# mother_card_cs_524pm.net
KiCad netlist of a schematic drawn in EAGLE
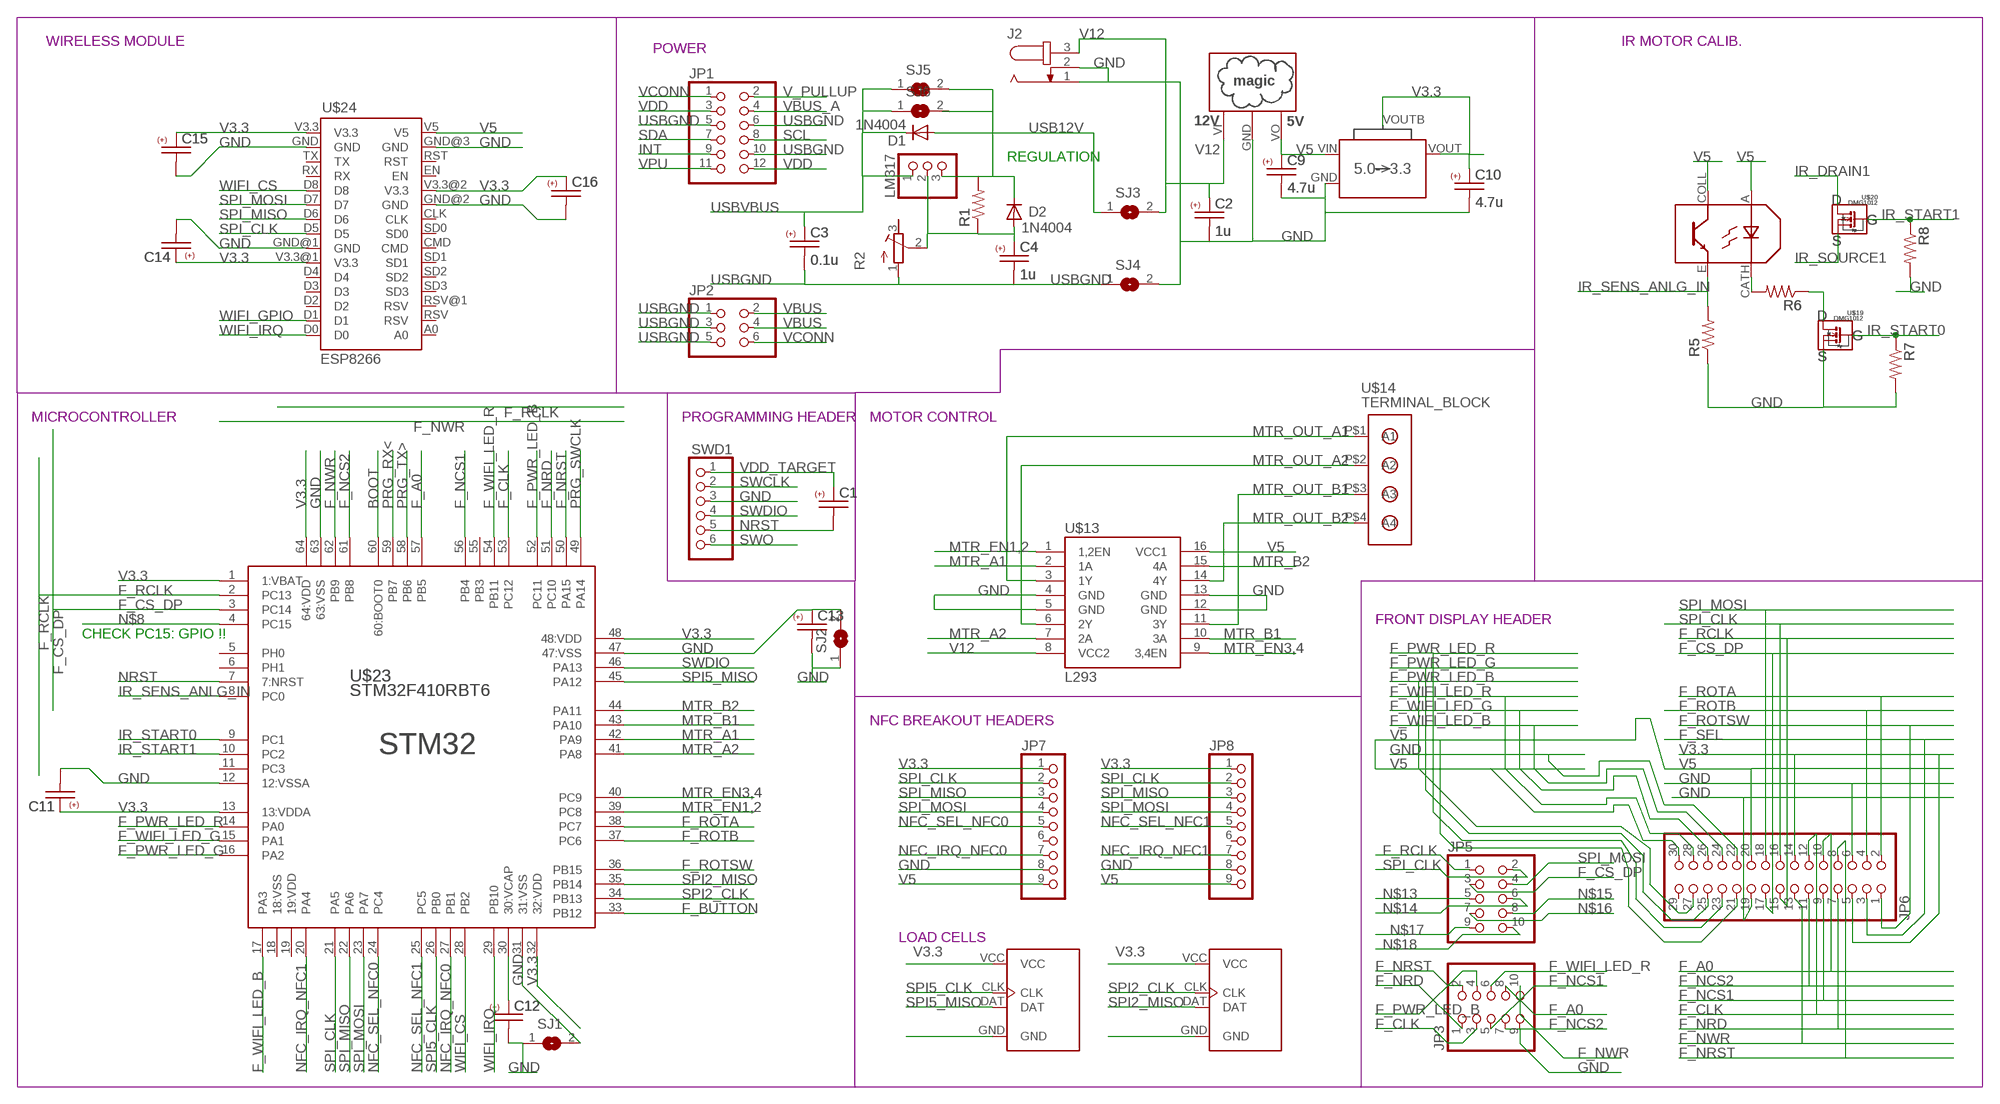
[diagram p0: schematic, sheet 1]

(export (version "E")
  (design (tool "Eeschema 10.0.6"))
  (components
    (comp (ref "C1")
      (value "C-USC0805")
      (footprint "eagle-import:C0805")
      (libsource (lib "eagle-import") (part "C-USC0805"))
    )
    (comp (ref "C2")
      (value "1u")
      (footprint "eagle-import:C0805")
      (libsource (lib "eagle-import") (part "C-USC0805"))
    )
    (comp (ref "C3")
      (value "0.1u")
      (footprint "eagle-import:C0805")
      (libsource (lib "eagle-import") (part "C-USC0805"))
    )
    (comp (ref "C4")
      (value "1u")
      (footprint "eagle-import:C0805")
      (libsource (lib "eagle-import") (part "C-USC0805"))
    )
    (comp (ref "C9")
      (value "4.7u")
      (footprint "eagle-import:C0805")
      (libsource (lib "eagle-import") (part "C-USC0805"))
    )
    (comp (ref "C10")
      (value "4.7u")
      (footprint "eagle-import:C0805")
      (libsource (lib "eagle-import") (part "C-USC0805"))
    )
    (comp (ref "C11")
      (value "C-USC0805")
      (footprint "eagle-import:C0805")
      (libsource (lib "eagle-import") (part "C-USC0805"))
    )
    (comp (ref "C12")
      (value "C-USC0805")
      (footprint "eagle-import:C0805")
      (libsource (lib "eagle-import") (part "C-USC0805"))
    )
    (comp (ref "C13")
      (value "C-USC0805")
      (footprint "eagle-import:C0805")
      (libsource (lib "eagle-import") (part "C-USC0805"))
    )
    (comp (ref "C14")
      (value "C-USC0805")
      (footprint "eagle-import:C0805")
      (libsource (lib "eagle-import") (part "C-USC0805"))
    )
    (comp (ref "C15")
      (value "C-USC0805")
      (footprint "eagle-import:C0805")
      (libsource (lib "eagle-import") (part "C-USC0805"))
    )
    (comp (ref "C16")
      (value "C-USC0805")
      (footprint "eagle-import:C0805")
      (libsource (lib "eagle-import") (part "C-USC0805"))
    )
    (comp (ref "D1")
      (value "1N4004")
      (footprint "eagle-import:DO41-10")
      (libsource (lib "eagle-import") (part "1N4004"))
    )
    (comp (ref "D2")
      (value "1N4004")
      (footprint "eagle-import:DO41-10")
      (libsource (lib "eagle-import") (part "1N4004"))
    )
    (comp (ref "J2")
      (value "JACK-PLUG0")
      (footprint "eagle-import:SPC4077")
      (libsource (lib "eagle-import") (part "JACK-PLUG0"))
    )
    (comp (ref "JP1")
      (value "PINHD-2X6")
      (footprint "eagle-import:2X06")
      (libsource (lib "eagle-import") (part "PINHD-2X6"))
    )
    (comp (ref "JP2")
      (value "PINHD-2X3")
      (footprint "eagle-import:2X03")
      (libsource (lib "eagle-import") (part "PINHD-2X3"))
    )
    (comp (ref "JP3")
      (value "PINHD-2X5")
      (footprint "eagle-import:2X05")
      (libsource (lib "eagle-import") (part "PINHD-2X5"))
    )
    (comp (ref "JP5")
      (value "PINHD-2X5")
      (footprint "eagle-import:2X05")
      (libsource (lib "eagle-import") (part "PINHD-2X5"))
    )
    (comp (ref "JP6")
      (value "PINHD-2X15/SOCK")
      (footprint "eagle-import:2X15_SOCK")
      (libsource (lib "eagle-import") (part "PINHD-2X15/SOCK"))
    )
    (comp (ref "JP7")
      (value "PINHD-1X9/90")
      (footprint "eagle-import:1X09_90")
      (libsource (lib "eagle-import") (part "PINHD-1X9/90"))
    )
    (comp (ref "JP8")
      (value "PINHD-1X9/90")
      (footprint "eagle-import:1X09_90")
      (libsource (lib "eagle-import") (part "PINHD-1X9/90"))
    )
    (comp (ref "LM317")
      (value "PINHD-1X3")
      (footprint "eagle-import:1X03")
      (libsource (lib "eagle-import") (part "PINHD-1X3"))
    )
    (comp (ref "R1")
      (value "R-US_R0805")
      (footprint "eagle-import:R0805")
      (libsource (lib "eagle-import") (part "R-US_R0805"))
    )
    (comp (ref "R2")
      (value "R-TRIMM64W")
      (footprint "eagle-import:RTRIM64W")
      (libsource (lib "eagle-import") (part "R-TRIMM64W"))
    )
    (comp (ref "R5")
      (value "R-US_R0805")
      (footprint "eagle-import:R0805")
      (libsource (lib "eagle-import") (part "R-US_R0805"))
    )
    (comp (ref "R6")
      (value "R-US_R0805")
      (footprint "eagle-import:R0805")
      (libsource (lib "eagle-import") (part "R-US_R0805"))
    )
    (comp (ref "R7")
      (value "R-US_R0805")
      (footprint "eagle-import:R0805")
      (libsource (lib "eagle-import") (part "R-US_R0805"))
    )
    (comp (ref "R8")
      (value "R-US_R0805")
      (footprint "eagle-import:R0805")
      (libsource (lib "eagle-import") (part "R-US_R0805"))
    )
    (comp (ref "SJ1") (value "SJ") (footprint "eagle-import:SJ") (libsource (lib "eagle-import") (part "SJ")))
    (comp (ref "SJ2") (value "SJ") (footprint "eagle-import:SJ") (libsource (lib "eagle-import") (part "SJ")))
    (comp (ref "SJ3") (value "SJ") (footprint "eagle-import:SJ") (libsource (lib "eagle-import") (part "SJ")))
    (comp (ref "SJ4") (value "SJ") (footprint "eagle-import:SJ") (libsource (lib "eagle-import") (part "SJ")))
    (comp (ref "SJ5") (value "SJ") (footprint "eagle-import:SJ") (libsource (lib "eagle-import") (part "SJ")))
    (comp (ref "SJ6") (value "SJ") (footprint "eagle-import:SJ") (libsource (lib "eagle-import") (part "SJ")))
    (comp (ref "SWD1")
      (value "PINHD-1X6")
      (footprint "eagle-import:1X06")
      (libsource (lib "eagle-import") (part "PINHD-1X6"))
    )
    (comp (ref "U$13")
      (value "L293")
      (footprint "eagle-import:DIL16")
      (libsource (lib "eagle-import") (part "L293"))
    )
    (comp (ref "U$14")
      (value "TERMINAL_BLOCK")
      (footprint "eagle-import:1X4_BLOCK")
      (libsource (lib "eagle-import") (part "TERMINAL_BLOCK"))
    )
    (comp (ref "U$15")
      (value "AP2114H")
      (footprint "eagle-import:AP2114H")
      (libsource (lib "eagle-import") (part "AP2114H"))
    )
    (comp (ref "U$16")
      (value "OKI-78SR-W36")
      (footprint "eagle-import:SIP3")
      (libsource (lib "eagle-import") (part "OKI-78SR-W36"))
    )
    (comp (ref "U$18")
      (value "TCRT5000")
      (footprint "eagle-import:TCRT5000")
      (libsource (lib "eagle-import") (part "TCRT5000"))
    )
    (comp (ref "U$19")
      (value "DMG1012")
      (footprint "eagle-import:SOT323")
      (libsource (lib "eagle-import") (part "DMG1012"))
    )
    (comp (ref "U$20")
      (value "DMG1012")
      (footprint "eagle-import:SOT323")
      (libsource (lib "eagle-import") (part "DMG1012"))
    )
    (comp (ref "U$21")
      (value "HX711")
      (footprint "eagle-import:HX711")
      (libsource (lib "eagle-import") (part "HX711"))
    )
    (comp (ref "U$22")
      (value "HX711")
      (footprint "eagle-import:HX711")
      (libsource (lib "eagle-import") (part "HX711"))
    )
    (comp (ref "U$23")
      (value "STM32F410RBT6")
      (footprint "eagle-import:QFP50P1200X1200X160-64N")
      (libsource (lib "eagle-import") (part "STM32F410RBT6"))
    )
    (comp (ref "U$24")
      (value "ESP8266")
      (footprint "eagle-import:ESP8266")
      (libsource (lib "eagle-import") (part "ESP8266"))
    )
  )
  (nets
    (net (code "1") (name "/BOOT") (class "Default")
      (node (ref "U$23") (pin "60") (pinfunction "60:BOOT0_60") (pintype "bidirectional"))
    )
    (net (code "2") (name "/F_A0") (class "Default")
      (node (ref "JP3") (pin "8") (pinfunction "8_8") (pintype "passive"))
      (node (ref "JP6") (pin "10") (pinfunction "10_10") (pintype "passive"))
      (node (ref "U$23") (pin "57") (pinfunction "PB5_57") (pintype "bidirectional"))
    )
    (net (code "3") (name "/F_BUTTON") (class "Default")
      (node (ref "U$23") (pin "33") (pinfunction "PB12_33") (pintype "bidirectional"))
    )
    (net (code "4") (name "/F_CLK") (class "Default")
      (node (ref "JP3") (pin "3") (pinfunction "3_3") (pintype "passive"))
      (node (ref "JP6") (pin "12") (pinfunction "12_12") (pintype "passive"))
      (node (ref "U$23") (pin "53") (pinfunction "PC12_53") (pintype "bidirectional"))
    )
    (net (code "5") (name "/F_CS_DP") (class "Default")
      (node (ref "JP5") (pin "3") (pinfunction "3_3") (pintype "passive"))
      (node (ref "JP6") (pin "17") (pinfunction "17_17") (pintype "passive"))
      (node (ref "U$23") (pin "3") (pinfunction "PC14_3") (pintype "bidirectional"))
    )
    (net (code "6") (name "/F_NCS1") (class "Default")
      (node (ref "JP3") (pin "5") (pinfunction "5_5") (pintype "passive"))
      (node (ref "JP6") (pin "9") (pinfunction "9_9") (pintype "passive"))
      (node (ref "U$23") (pin "56") (pinfunction "PB4_56") (pintype "bidirectional"))
    )
    (net (code "7") (name "/F_NCS2") (class "Default")
      (node (ref "JP3") (pin "7") (pinfunction "7_7") (pintype "passive"))
      (node (ref "JP6") (pin "11") (pinfunction "11_11") (pintype "passive"))
      (node (ref "U$23") (pin "61") (pinfunction "PB8_61") (pintype "bidirectional"))
    )
    (net (code "8") (name "/F_NRD") (class "Default")
      (node (ref "JP3") (pin "1") (pinfunction "1_1") (pintype "passive"))
      (node (ref "JP6") (pin "7") (pinfunction "7_7") (pintype "passive"))
      (node (ref "U$23") (pin "51") (pinfunction "PC10_51") (pintype "bidirectional"))
    )
    (net (code "9") (name "/F_NRST") (class "Default")
      (node (ref "JP3") (pin "2") (pinfunction "2_2") (pintype "passive"))
      (node (ref "JP6") (pin "8") (pinfunction "8_8") (pintype "passive"))
      (node (ref "U$23") (pin "50") (pinfunction "PA15_50") (pintype "bidirectional"))
    )
    (net (code "10") (name "/F_NWR") (class "Default")
      (node (ref "JP3") (pin "10") (pinfunction "10_10") (pintype "passive"))
      (node (ref "JP6") (pin "13") (pinfunction "13_13") (pintype "passive"))
      (node (ref "U$23") (pin "62") (pinfunction "PB9_62") (pintype "bidirectional"))
    )
    (net (code "11") (name "/F_PWR_LED_B") (class "Default")
      (node (ref "JP3") (pin "4") (pinfunction "4_4") (pintype "passive"))
      (node (ref "JP6") (pin "27") (pinfunction "27_27") (pintype "passive"))
      (node (ref "U$23") (pin "52") (pinfunction "PC11_52") (pintype "bidirectional"))
    )
    (net (code "12") (name "/F_PWR_LED_G") (class "Default")
      (node (ref "JP6") (pin "25") (pinfunction "25_25") (pintype "passive"))
      (node (ref "U$23") (pin "16") (pinfunction "PA2_16") (pintype "bidirectional"))
    )
    (net (code "13") (name "/F_PWR_LED_R") (class "Default")
      (node (ref "JP6") (pin "23") (pinfunction "23_23") (pintype "passive"))
      (node (ref "U$23") (pin "14") (pinfunction "PA0_14") (pintype "bidirectional"))
    )
    (net (code "14") (name "/F_RCLK") (class "Default")
      (node (ref "JP5") (pin "1") (pinfunction "1_1") (pintype "passive"))
      (node (ref "JP6") (pin "15") (pinfunction "15_15") (pintype "passive"))
      (node (ref "U$23") (pin "2") (pinfunction "PC13_2") (pintype "bidirectional"))
    )
    (net (code "15") (name "/F_ROTA") (class "Default")
      (node (ref "JP6") (pin "2") (pinfunction "2_2") (pintype "passive"))
      (node (ref "U$23") (pin "38") (pinfunction "PC7_38") (pintype "bidirectional"))
    )
    (net (code "16") (name "/F_ROTB") (class "Default")
      (node (ref "JP6") (pin "4") (pinfunction "4_4") (pintype "passive"))
      (node (ref "U$23") (pin "37") (pinfunction "PC6_37") (pintype "bidirectional"))
    )
    (net (code "17") (name "/F_ROTSW") (class "Default")
      (node (ref "JP6") (pin "1") (pinfunction "1_1") (pintype "passive"))
      (node (ref "U$23") (pin "36") (pinfunction "PB15_36") (pintype "bidirectional"))
    )
    (net (code "18") (name "/F_SEL") (class "Default")
      (node (ref "JP6") (pin "3") (pinfunction "3_3") (pintype "passive"))
    )
    (net (code "19") (name "/F_WIFI_LED_B") (class "Default")
      (node (ref "JP6") (pin "24") (pinfunction "24_24") (pintype "passive"))
      (node (ref "U$23") (pin "17") (pinfunction "PA3_17") (pintype "bidirectional"))
    )
    (net (code "20") (name "/F_WIFI_LED_G") (class "Default")
      (node (ref "JP6") (pin "26") (pinfunction "26_26") (pintype "passive"))
      (node (ref "U$23") (pin "15") (pinfunction "PA1_15") (pintype "bidirectional"))
    )
    (net (code "21") (name "/F_WIFI_LED_R") (class "Default")
      (node (ref "JP3") (pin "6") (pinfunction "6_6") (pintype "passive"))
      (node (ref "JP6") (pin "28") (pinfunction "28_28") (pintype "passive"))
      (node (ref "U$23") (pin "54") (pinfunction "PB11_54") (pintype "bidirectional"))
    )
    (net (code "22") (name "/GND") (class "Default")
      (node (ref "C10") (pin "2") (pinfunction "2_2") (pintype "passive"))
      (node (ref "C11") (pin "2") (pinfunction "2_2") (pintype "passive"))
      (node (ref "C12") (pin "2") (pinfunction "2_2") (pintype "passive"))
      (node (ref "C13") (pin "1") (pinfunction "1_1") (pintype "passive"))
      (node (ref "C14") (pin "2") (pinfunction "2_2") (pintype "passive"))
      (node (ref "C15") (pin "2") (pinfunction "2_2") (pintype "passive"))
      (node (ref "C16") (pin "2") (pinfunction "2_2") (pintype "passive"))
      (node (ref "C2") (pin "2") (pinfunction "2_2") (pintype "passive"))
      (node (ref "C9") (pin "2") (pinfunction "2_2") (pintype "passive"))
      (node (ref "J2") (pin "1") (pinfunction "1_1") (pintype "passive"))
      (node (ref "J2") (pin "2") (pinfunction "2_2") (pintype "passive"))
      (node (ref "JP3") (pin "9") (pinfunction "9_9") (pintype "passive"))
      (node (ref "JP6") (pin "19") (pinfunction "19_19") (pintype "passive"))
      (node (ref "JP6") (pin "22") (pinfunction "22_22") (pintype "passive"))
      (node (ref "JP6") (pin "6") (pinfunction "6_6") (pintype "passive"))
      (node (ref "JP7") (pin "8") (pinfunction "8_8") (pintype "passive"))
      (node (ref "JP8") (pin "8") (pinfunction "8_8") (pintype "passive"))
      (node (ref "R5") (pin "1") (pinfunction "1_1") (pintype "passive"))
      (node (ref "R7") (pin "2") (pinfunction "2_2") (pintype "passive"))
      (node (ref "R8") (pin "2") (pinfunction "2_2") (pintype "passive"))
      (node (ref "SJ1") (pin "1") (pinfunction "1_1") (pintype "passive"))
      (node (ref "SJ1") (pin "2") (pinfunction "2_2") (pintype "passive"))
      (node (ref "SJ2") (pin "2") (pinfunction "2_2") (pintype "passive"))
      (node (ref "SJ4") (pin "2") (pinfunction "2_2") (pintype "passive"))
      (node (ref "SWD1") (pin "3") (pinfunction "3_3") (pintype "passive"))
      (node (ref "U$13") (pin "12") (pinfunction "GND_12") (pintype "bidirectional"))
      (node (ref "U$13") (pin "13") (pinfunction "GND_13") (pintype "bidirectional"))
      (node (ref "U$13") (pin "4") (pinfunction "GND_4") (pintype "bidirectional"))
      (node (ref "U$13") (pin "5") (pinfunction "GND_5") (pintype "bidirectional"))
      (node (ref "U$15") (pin "GND") (pinfunction "GND_GND") (pintype "power_in"))
      (node (ref "U$16") (pin "GND") (pinfunction "P$2_GND") (pintype "power_in"))
      (node (ref "U$19") (pin "S") (pinfunction "S_S") (pintype "bidirectional"))
      (node (ref "U$21") (pin "GND") (pinfunction "GND_GND") (pintype "power_in"))
      (node (ref "U$22") (pin "GND") (pinfunction "GND_GND") (pintype "power_in"))
      (node (ref "U$23") (pin "12") (pinfunction "12:VSSA_12") (pintype "bidirectional"))
      (node (ref "U$23") (pin "31") (pinfunction "31:VSS_31") (pintype "bidirectional"))
      (node (ref "U$23") (pin "47") (pinfunction "47:VSS_47") (pintype "bidirectional"))
      (node (ref "U$23") (pin "63") (pinfunction "63:VSS_63") (pintype "bidirectional"))
      (node (ref "U$24") (pin "GND") (pinfunction "GND_GND") (pintype "bidirectional"))
      (node (ref "U$24") (pin "GND@1") (pinfunction "GND_GND@1") (pintype "bidirectional"))
      (node (ref "U$24") (pin "GND@2") (pinfunction "GND_GND@2") (pintype "bidirectional"))
      (node (ref "U$24") (pin "GND@3") (pinfunction "GND_GND@3") (pintype "bidirectional"))
    )
    (net (code "23") (name "/INT") (class "Default")
      (node (ref "JP1") (pin "9") (pinfunction "9_9") (pintype "passive"))
    )
    (net (code "24") (name "/IR_DRAIN1") (class "Default")
      (node (ref "U$20") (pin "D") (pinfunction "D_D") (pintype "bidirectional"))
    )
    (net (code "25") (name "/IR_SENS_ANLG_IN") (class "Default")
      (node (ref "R5") (pin "2") (pinfunction "2_2") (pintype "passive"))
      (node (ref "U$18") (pin "E") (pinfunction "E_E") (pintype "bidirectional"))
      (node (ref "U$23") (pin "8") (pinfunction "PC0_8") (pintype "bidirectional"))
    )
    (net (code "26") (name "/IR_SOURCE1") (class "Default")
      (node (ref "U$20") (pin "S") (pinfunction "S_S") (pintype "bidirectional"))
    )
    (net (code "27") (name "/IR_START0") (class "Default")
      (node (ref "R7") (pin "1") (pinfunction "1_1") (pintype "passive"))
      (node (ref "U$19") (pin "G") (pinfunction "G_G") (pintype "bidirectional"))
      (node (ref "U$23") (pin "9") (pinfunction "PC1_9") (pintype "bidirectional"))
    )
    (net (code "28") (name "/IR_START1") (class "Default")
      (node (ref "R8") (pin "1") (pinfunction "1_1") (pintype "passive"))
      (node (ref "U$20") (pin "G") (pinfunction "G_G") (pintype "bidirectional"))
      (node (ref "U$23") (pin "10") (pinfunction "PC2_10") (pintype "bidirectional"))
    )
    (net (code "29") (name "/MTR_A1") (class "Default")
      (node (ref "U$13") (pin "2") (pinfunction "1A_2") (pintype "bidirectional"))
      (node (ref "U$23") (pin "42") (pinfunction "PA9_42") (pintype "bidirectional"))
    )
    (net (code "30") (name "/MTR_A2") (class "Default")
      (node (ref "U$13") (pin "7") (pinfunction "2A_7") (pintype "bidirectional"))
      (node (ref "U$23") (pin "41") (pinfunction "PA8_41") (pintype "bidirectional"))
    )
    (net (code "31") (name "/MTR_B1") (class "Default")
      (node (ref "U$13") (pin "10") (pinfunction "3A_10") (pintype "bidirectional"))
      (node (ref "U$23") (pin "43") (pinfunction "PA10_43") (pintype "bidirectional"))
    )
    (net (code "32") (name "/MTR_B2") (class "Default")
      (node (ref "U$13") (pin "15") (pinfunction "4A_15") (pintype "bidirectional"))
      (node (ref "U$23") (pin "44") (pinfunction "PA11_44") (pintype "bidirectional"))
    )
    (net (code "33") (name "/MTR_EN1,2") (class "Default")
      (node (ref "U$13") (pin "1") (pinfunction "1,2EN_1") (pintype "bidirectional"))
      (node (ref "U$23") (pin "39") (pinfunction "PC8_39") (pintype "bidirectional"))
    )
    (net (code "34") (name "/MTR_EN3,4") (class "Default")
      (node (ref "U$13") (pin "9") (pinfunction "3,4EN_9") (pintype "bidirectional"))
      (node (ref "U$23") (pin "40") (pinfunction "PC9_40") (pintype "bidirectional"))
    )
    (net (code "35") (name "/MTR_OUT_A1") (class "Default")
      (node (ref "U$13") (pin "3") (pinfunction "1Y_3") (pintype "bidirectional"))
      (node (ref "U$14") (pin "P$1") (pinfunction "A1_P$1") (pintype "bidirectional"))
    )
    (net (code "36") (name "/MTR_OUT_A2") (class "Default")
      (node (ref "U$13") (pin "6") (pinfunction "2Y_6") (pintype "bidirectional"))
      (node (ref "U$14") (pin "P$2") (pinfunction "A2_P$2") (pintype "bidirectional"))
    )
    (net (code "37") (name "/MTR_OUT_B1") (class "Default")
      (node (ref "U$13") (pin "11") (pinfunction "3Y_11") (pintype "bidirectional"))
      (node (ref "U$14") (pin "P$3") (pinfunction "A3_P$3") (pintype "bidirectional"))
    )
    (net (code "38") (name "/MTR_OUT_B2") (class "Default")
      (node (ref "U$13") (pin "14") (pinfunction "4Y_14") (pintype "bidirectional"))
      (node (ref "U$14") (pin "P$4") (pinfunction "A4_P$4") (pintype "bidirectional"))
    )
    (net (code "39") (name "/N$8") (class "Default")
      (node (ref "U$23") (pin "4") (pinfunction "PC15_4") (pintype "bidirectional"))
    )
    (net (code "40") (name "/N$13") (class "Default")
      (node (ref "JP5") (pin "5") (pinfunction "5_5") (pintype "passive"))
    )
    (net (code "41") (name "/N$14") (class "Default")
      (node (ref "JP5") (pin "6") (pinfunction "6_6") (pintype "passive"))
    )
    (net (code "42") (name "/N$15") (class "Default")
      (node (ref "JP5") (pin "8") (pinfunction "8_8") (pintype "passive"))
    )
    (net (code "43") (name "/N$16") (class "Default")
      (node (ref "JP5") (pin "7") (pinfunction "7_7") (pintype "passive"))
    )
    (net (code "44") (name "/N$17") (class "Default")
      (node (ref "JP5") (pin "9") (pinfunction "9_9") (pintype "passive"))
    )
    (net (code "45") (name "/N$18") (class "Default")
      (node (ref "JP5") (pin "10") (pinfunction "10_10") (pintype "passive"))
    )
    (net (code "46") (name "/NFC_IRQ_NFC0") (class "Default")
      (node (ref "JP7") (pin "7") (pinfunction "7_7") (pintype "passive"))
      (node (ref "U$23") (pin "27") (pinfunction "PB1_27") (pintype "bidirectional"))
    )
    (net (code "47") (name "/NFC_IRQ_NFC1") (class "Default")
      (node (ref "JP8") (pin "7") (pinfunction "7_7") (pintype "passive"))
      (node (ref "U$23") (pin "20") (pinfunction "PA4_20") (pintype "bidirectional"))
    )
    (net (code "48") (name "/NFC_SEL_NFC0") (class "Default")
      (node (ref "JP7") (pin "5") (pinfunction "5_5") (pintype "passive"))
      (node (ref "U$23") (pin "24") (pinfunction "PC4_24") (pintype "bidirectional"))
    )
    (net (code "49") (name "/NFC_SEL_NFC1") (class "Default")
      (node (ref "JP8") (pin "5") (pinfunction "5_5") (pintype "passive"))
      (node (ref "U$23") (pin "25") (pinfunction "PC5_25") (pintype "bidirectional"))
    )
    (net (code "50") (name "/NRST") (class "Default")
      (node (ref "C1") (pin "2") (pinfunction "2_2") (pintype "passive"))
      (node (ref "SWD1") (pin "5") (pinfunction "5_5") (pintype "passive"))
      (node (ref "U$23") (pin "7") (pinfunction "7:NRST_7") (pintype "bidirectional"))
    )
    (net (code "51") (name "/PRG_RX<") (class "Default")
      (node (ref "U$23") (pin "59") (pinfunction "PB7_59") (pintype "bidirectional"))
    )
    (net (code "52") (name "/PRG_SWCLK") (class "Default")
      (node (ref "U$23") (pin "49") (pinfunction "PA14_49") (pintype "bidirectional"))
    )
    (net (code "53") (name "/PRG_TX>") (class "Default")
      (node (ref "U$23") (pin "58") (pinfunction "PB6_58") (pintype "bidirectional"))
    )
    (net (code "54") (name "/SCL") (class "Default")
      (node (ref "JP1") (pin "8") (pinfunction "8_8") (pintype "passive"))
    )
    (net (code "55") (name "/SDA") (class "Default")
      (node (ref "JP1") (pin "7") (pinfunction "7_7") (pintype "passive"))
    )
    (net (code "56") (name "/SPI2_CLK") (class "Default")
      (node (ref "U$22") (pin "CLK") (pinfunction "CLK_CLK") (pintype "bidirectional"))
      (node (ref "U$23") (pin "34") (pinfunction "PB13_34") (pintype "bidirectional"))
    )
    (net (code "57") (name "/SPI2_MISO") (class "Default")
      (node (ref "U$22") (pin "DAT") (pinfunction "DAT_DAT") (pintype "bidirectional"))
      (node (ref "U$23") (pin "35") (pinfunction "PB14_35") (pintype "bidirectional"))
    )
    (net (code "58") (name "/SPI5_CLK") (class "Default")
      (node (ref "U$21") (pin "CLK") (pinfunction "CLK_CLK") (pintype "bidirectional"))
      (node (ref "U$23") (pin "26") (pinfunction "PB0_26") (pintype "bidirectional"))
    )
    (net (code "59") (name "/SPI5_MISO") (class "Default")
      (node (ref "U$21") (pin "DAT") (pinfunction "DAT_DAT") (pintype "bidirectional"))
      (node (ref "U$23") (pin "45") (pinfunction "PA12_45") (pintype "bidirectional"))
    )
    (net (code "60") (name "/SPI_CLK") (class "Default")
      (node (ref "JP5") (pin "2") (pinfunction "2_2") (pintype "passive"))
      (node (ref "JP6") (pin "16") (pinfunction "16_16") (pintype "passive"))
      (node (ref "JP7") (pin "2") (pinfunction "2_2") (pintype "passive"))
      (node (ref "JP8") (pin "2") (pinfunction "2_2") (pintype "passive"))
      (node (ref "U$23") (pin "21") (pinfunction "PA5_21") (pintype "bidirectional"))
      (node (ref "U$24") (pin "D5") (pinfunction "D5_D5") (pintype "bidirectional"))
    )
    (net (code "61") (name "/SPI_MISO") (class "Default")
      (node (ref "JP7") (pin "3") (pinfunction "3_3") (pintype "passive"))
      (node (ref "JP8") (pin "3") (pinfunction "3_3") (pintype "passive"))
      (node (ref "U$23") (pin "22") (pinfunction "PA6_22") (pintype "bidirectional"))
      (node (ref "U$24") (pin "D6") (pinfunction "D6_D6") (pintype "bidirectional"))
    )
    (net (code "62") (name "/SPI_MOSI") (class "Default")
      (node (ref "JP5") (pin "4") (pinfunction "4_4") (pintype "passive"))
      (node (ref "JP6") (pin "18") (pinfunction "18_18") (pintype "passive"))
      (node (ref "JP7") (pin "4") (pinfunction "4_4") (pintype "passive"))
      (node (ref "JP8") (pin "4") (pinfunction "4_4") (pintype "passive"))
      (node (ref "U$23") (pin "23") (pinfunction "PA7_23") (pintype "bidirectional"))
      (node (ref "U$24") (pin "D7") (pinfunction "D7_D7") (pintype "bidirectional"))
    )
    (net (code "63") (name "/SWCLK") (class "Default")
      (node (ref "SWD1") (pin "2") (pinfunction "2_2") (pintype "passive"))
    )
    (net (code "64") (name "/SWDIO") (class "Default")
      (node (ref "SWD1") (pin "4") (pinfunction "4_4") (pintype "passive"))
      (node (ref "U$23") (pin "46") (pinfunction "PA13_46") (pintype "bidirectional"))
    )
    (net (code "65") (name "/SWO") (class "Default")
      (node (ref "SWD1") (pin "6") (pinfunction "6_6") (pintype "passive"))
    )
    (net (code "66") (name "/USB12V") (class "Default")
      (node (ref "D1") (pin "A") (pinfunction "A_A") (pintype "passive"))
      (node (ref "D2") (pin "C") (pinfunction "C_C") (pintype "passive"))
      (node (ref "LM317") (pin "3") (pinfunction "3_3") (pintype "passive"))
      (node (ref "R1") (pin "2") (pinfunction "2_2") (pintype "passive"))
      (node (ref "SJ3") (pin "1") (pinfunction "1_1") (pintype "passive"))
      (node (ref "SJ5") (pin "2") (pinfunction "2_2") (pintype "passive"))
    )
    (net (code "67") (name "/USBGND") (class "Default")
      (node (ref "C3") (pin "2") (pinfunction "2_2") (pintype "passive"))
      (node (ref "C4") (pin "2") (pinfunction "2_2") (pintype "passive"))
      (node (ref "JP1") (pin "10") (pinfunction "10_10") (pintype "passive"))
      (node (ref "JP1") (pin "5") (pinfunction "5_5") (pintype "passive"))
      (node (ref "JP1") (pin "6") (pinfunction "6_6") (pintype "passive"))
      (node (ref "JP2") (pin "1") (pinfunction "1_1") (pintype "passive"))
      (node (ref "JP2") (pin "3") (pinfunction "3_3") (pintype "passive"))
      (node (ref "JP2") (pin "5") (pinfunction "5_5") (pintype "passive"))
      (node (ref "R2") (pin "1") (pinfunction "A_1") (pintype "passive"))
      (node (ref "SJ4") (pin "1") (pinfunction "1_1") (pintype "passive"))
    )
    (net (code "68") (name "/USBVBUS") (class "Default")
      (node (ref "C3") (pin "1") (pinfunction "1_1") (pintype "passive"))
      (node (ref "D1") (pin "C") (pinfunction "C_C") (pintype "passive"))
      (node (ref "LM317") (pin "1") (pinfunction "1_1") (pintype "passive"))
      (node (ref "SJ5") (pin "1") (pinfunction "1_1") (pintype "passive"))
      (node (ref "SJ6") (pin "1") (pinfunction "1_1") (pintype "passive"))
    )
    (net (code "69") (name "/V3.3") (class "Default")
      (node (ref "C10") (pin "1") (pinfunction "1_1") (pintype "passive"))
      (node (ref "C11") (pin "1") (pinfunction "1_1") (pintype "passive"))
      (node (ref "C14") (pin "1") (pinfunction "1_1") (pintype "passive"))
      (node (ref "C15") (pin "1") (pinfunction "1_1") (pintype "passive"))
      (node (ref "C16") (pin "1") (pinfunction "1_1") (pintype "passive"))
      (node (ref "JP6") (pin "14") (pinfunction "14_14") (pintype "passive"))
      (node (ref "JP6") (pin "5") (pinfunction "5_5") (pintype "passive"))
      (node (ref "JP7") (pin "1") (pinfunction "1_1") (pintype "passive"))
      (node (ref "JP8") (pin "1") (pinfunction "1_1") (pintype "passive"))
      (node (ref "U$15") (pin "VOUT") (pinfunction "VO_VOUT") (pintype "output"))
      (node (ref "U$15") (pin "VOUTB") (pinfunction "BODY_VOUTB") (pintype "open_collector"))
      (node (ref "U$21") (pin "VCC") (pinfunction "VCC_VCC") (pintype "power_in"))
      (node (ref "U$22") (pin "VCC") (pinfunction "VCC_VCC") (pintype "power_in"))
      (node (ref "U$23") (pin "1") (pinfunction "1:VBAT_1") (pintype "bidirectional"))
      (node (ref "U$23") (pin "13") (pinfunction "13:VDDA_13") (pintype "bidirectional"))
      (node (ref "U$23") (pin "32") (pinfunction "32:VDD_32") (pintype "bidirectional"))
      (node (ref "U$23") (pin "48") (pinfunction "48:VDD_48") (pintype "bidirectional"))
      (node (ref "U$23") (pin "64") (pinfunction "64:VDD_64") (pintype "bidirectional"))
      (node (ref "U$24") (pin "V3.3") (pinfunction "V3.3_V3.3") (pintype "bidirectional"))
      (node (ref "U$24") (pin "V3.3@1") (pinfunction "V3.3_V3.3@1") (pintype "bidirectional"))
      (node (ref "U$24") (pin "V3.3@2") (pinfunction "V3.3_V3.3@2") (pintype "bidirectional"))
    )
    (net (code "70") (name "/V5") (class "Default")
      (node (ref "C9") (pin "1") (pinfunction "1_1") (pintype "passive"))
      (node (ref "JP6") (pin "20") (pinfunction "20_20") (pintype "passive"))
      (node (ref "JP6") (pin "21") (pinfunction "21_21") (pintype "passive"))
      (node (ref "JP6") (pin "30") (pinfunction "30_30") (pintype "passive"))
      (node (ref "JP7") (pin "9") (pinfunction "9_9") (pintype "passive"))
      (node (ref "JP8") (pin "9") (pinfunction "9_9") (pintype "passive"))
      (node (ref "U$13") (pin "16") (pinfunction "VCC1_16") (pintype "bidirectional"))
      (node (ref "U$15") (pin "VIN") (pinfunction "VI_VIN") (pintype "input"))
      (node (ref "U$16") (pin "VO") (pinfunction "P$3_VO") (pintype "output"))
      (node (ref "U$18") (pin "A") (pinfunction "A_A") (pintype "bidirectional"))
      (node (ref "U$18") (pin "COLL") (pinfunction "COLL_COLL") (pintype "bidirectional"))
      (node (ref "U$24") (pin "V5") (pinfunction "V5_V5") (pintype "bidirectional"))
    )
    (net (code "71") (name "/V12") (class "Default")
      (node (ref "C2") (pin "1") (pinfunction "1_1") (pintype "passive"))
      (node (ref "J2") (pin "3") (pinfunction "3_3") (pintype "passive"))
      (node (ref "SJ3") (pin "2") (pinfunction "2_2") (pintype "passive"))
      (node (ref "U$13") (pin "8") (pinfunction "VCC2_8") (pintype "bidirectional"))
      (node (ref "U$16") (pin "VI") (pinfunction "P$1_VI") (pintype "input"))
    )
    (net (code "72") (name "/VBUS") (class "Default")
      (node (ref "JP2") (pin "2") (pinfunction "2_2") (pintype "passive"))
      (node (ref "JP2") (pin "4") (pinfunction "4_4") (pintype "passive"))
    )
    (net (code "73") (name "/VBUS_A") (class "Default")
      (node (ref "JP1") (pin "4") (pinfunction "4_4") (pintype "passive"))
    )
    (net (code "74") (name "/VCONN") (class "Default")
      (node (ref "JP1") (pin "1") (pinfunction "1_1") (pintype "passive"))
      (node (ref "JP2") (pin "6") (pinfunction "6_6") (pintype "passive"))
    )
    (net (code "75") (name "/VDD") (class "Default")
      (node (ref "JP1") (pin "12") (pinfunction "12_12") (pintype "passive"))
      (node (ref "JP1") (pin "3") (pinfunction "3_3") (pintype "passive"))
    )
    (net (code "76") (name "/VDD_TARGET") (class "Default")
      (node (ref "C1") (pin "1") (pinfunction "1_1") (pintype "passive"))
      (node (ref "SWD1") (pin "1") (pinfunction "1_1") (pintype "passive"))
    )
    (net (code "77") (name "/VPU") (class "Default")
      (node (ref "JP1") (pin "11") (pinfunction "11_11") (pintype "passive"))
    )
    (net (code "78") (name "/V_PULLUP") (class "Default")
      (node (ref "JP1") (pin "2") (pinfunction "2_2") (pintype "passive"))
    )
    (net (code "79") (name "/WIFI_CS") (class "Default")
      (node (ref "U$23") (pin "28") (pinfunction "PB2_28") (pintype "bidirectional"))
      (node (ref "U$24") (pin "D8") (pinfunction "D8_D8") (pintype "bidirectional"))
    )
    (net (code "80") (name "/WIFI_GPIO") (class "Default")
      (node (ref "U$24") (pin "D1") (pinfunction "D1_D1") (pintype "bidirectional"))
    )
    (net (code "81") (name "/WIFI_IRQ") (class "Default")
      (node (ref "U$23") (pin "29") (pinfunction "PB10_29") (pintype "bidirectional"))
      (node (ref "U$24") (pin "D0") (pinfunction "D0_D0") (pintype "bidirectional"))
    )
    (net (code "82") (name "Net-(C13-Pad2)") (class "Default")
      (node (ref "C13") (pin "2") (pinfunction "2_2") (pintype "passive"))
      (node (ref "SJ2") (pin "1") (pinfunction "1_1") (pintype "passive"))
    )
    (net (code "83") (name "Net-(R2-S)") (class "Default")
      (node (ref "C4") (pin "1") (pinfunction "1_1") (pintype "passive"))
      (node (ref "D2") (pin "A") (pinfunction "A_A") (pintype "passive"))
      (node (ref "LM317") (pin "2") (pinfunction "2_2") (pintype "passive"))
      (node (ref "R1") (pin "1") (pinfunction "1_1") (pintype "passive"))
      (node (ref "R2") (pin "2") (pinfunction "S_2") (pintype "passive"))
    )
    (net (code "84") (name "Net-(R6-Pad1)") (class "Default")
      (node (ref "R6") (pin "1") (pinfunction "1_1") (pintype "passive"))
      (node (ref "U$19") (pin "D") (pinfunction "D_D") (pintype "bidirectional"))
    )
    (net (code "85") (name "Net-(R6-Pad2)") (class "Default")
      (node (ref "R6") (pin "2") (pinfunction "2_2") (pintype "passive"))
      (node (ref "U$18") (pin "CATH") (pinfunction "CATH_CATH") (pintype "bidirectional"))
    )
    (net (code "86") (name "Net-(U$23-30:VCAP)") (class "Default")
      (node (ref "C12") (pin "1") (pinfunction "1_1") (pintype "passive"))
      (node (ref "U$23") (pin "30") (pinfunction "30:VCAP_30") (pintype "bidirectional"))
    )
    (net (code "87") (name "unconnected-(JP6-Pad29)") (class "Default")
      (node (ref "JP6") (pin "29") (pinfunction "29_29") (pintype "passive"))
    )
    (net (code "88") (name "unconnected-(JP7-Pad6)") (class "Default")
      (node (ref "JP7") (pin "6") (pinfunction "6_6") (pintype "passive"))
    )
    (net (code "89") (name "unconnected-(JP8-Pad6)") (class "Default")
      (node (ref "JP8") (pin "6") (pinfunction "6_6") (pintype "passive"))
    )
    (net (code "90") (name "unconnected-(R2-E-Pad3)") (class "Default")
      (node (ref "R2") (pin "3") (pinfunction "E_3") (pintype "passive"))
    )
    (net (code "91") (name "unconnected-(SJ6-Pad2)") (class "Default")
      (node (ref "SJ6") (pin "2") (pinfunction "2_2") (pintype "passive"))
    )
    (net (code "92") (name "unconnected-(U$23-18:VSS-Pad18)") (class "Default")
      (node (ref "U$23") (pin "18") (pinfunction "18:VSS_18") (pintype "bidirectional"))
    )
    (net (code "93") (name "unconnected-(U$23-19:VDD-Pad19)") (class "Default")
      (node (ref "U$23") (pin "19") (pinfunction "19:VDD_19") (pintype "bidirectional"))
    )
    (net (code "94") (name "unconnected-(U$23-PB3-Pad55)") (class "Default")
      (node (ref "U$23") (pin "55") (pinfunction "PB3_55") (pintype "bidirectional"))
    )
    (net (code "95") (name "unconnected-(U$23-PC3-Pad11)") (class "Default")
      (node (ref "U$23") (pin "11") (pinfunction "PC3_11") (pintype "bidirectional"))
    )
    (net (code "96") (name "unconnected-(U$23-PH0-Pad5)") (class "Default")
      (node (ref "U$23") (pin "5") (pinfunction "PH0_5") (pintype "bidirectional"))
    )
    (net (code "97") (name "unconnected-(U$23-PH1-Pad6)") (class "Default")
      (node (ref "U$23") (pin "6") (pinfunction "PH1_6") (pintype "bidirectional"))
    )
    (net (code "98") (name "unconnected-(U$24-PadA0)") (class "Default")
      (node (ref "U$24") (pin "A0") (pinfunction "A0_A0") (pintype "bidirectional"))
    )
    (net (code "99") (name "unconnected-(U$24-PadCLK)") (class "Default")
      (node (ref "U$24") (pin "CLK") (pinfunction "CLK_CLK") (pintype "bidirectional"))
    )
    (net (code "100") (name "unconnected-(U$24-PadCMD)") (class "Default")
      (node (ref "U$24") (pin "CMD") (pinfunction "CMD_CMD") (pintype "bidirectional"))
    )
    (net (code "101") (name "unconnected-(U$24-PadD2)") (class "Default")
      (node (ref "U$24") (pin "D2") (pinfunction "D2_D2") (pintype "bidirectional"))
    )
    (net (code "102") (name "unconnected-(U$24-PadD3)") (class "Default")
      (node (ref "U$24") (pin "D3") (pinfunction "D3_D3") (pintype "bidirectional"))
    )
    (net (code "103") (name "unconnected-(U$24-PadD4)") (class "Default")
      (node (ref "U$24") (pin "D4") (pinfunction "D4_D4") (pintype "bidirectional"))
    )
    (net (code "104") (name "unconnected-(U$24-PadEN)") (class "Default")
      (node (ref "U$24") (pin "EN") (pinfunction "EN_EN") (pintype "bidirectional"))
    )
    (net (code "105") (name "unconnected-(U$24-PadRST)") (class "Default")
      (node (ref "U$24") (pin "RST") (pinfunction "RST_RST") (pintype "bidirectional"))
    )
    (net (code "106") (name "unconnected-(U$24-PadRSV)") (class "Default")
      (node (ref "U$24") (pin "RSV") (pinfunction "RSV_RSV") (pintype "bidirectional"))
    )
    (net (code "107") (name "unconnected-(U$24-PadRX)") (class "Default")
      (node (ref "U$24") (pin "RX") (pinfunction "RX_RX") (pintype "bidirectional"))
    )
    (net (code "108") (name "unconnected-(U$24-PadSD0)") (class "Default")
      (node (ref "U$24") (pin "SD0") (pinfunction "SD0_SD0") (pintype "bidirectional"))
    )
    (net (code "109") (name "unconnected-(U$24-PadSD1)") (class "Default")
      (node (ref "U$24") (pin "SD1") (pinfunction "SD1_SD1") (pintype "bidirectional"))
    )
    (net (code "110") (name "unconnected-(U$24-PadSD2)") (class "Default")
      (node (ref "U$24") (pin "SD2") (pinfunction "SD2_SD2") (pintype "bidirectional"))
    )
    (net (code "111") (name "unconnected-(U$24-PadSD3)") (class "Default")
      (node (ref "U$24") (pin "SD3") (pinfunction "SD3_SD3") (pintype "bidirectional"))
    )
    (net (code "112") (name "unconnected-(U$24-PadTX)") (class "Default")
      (node (ref "U$24") (pin "TX") (pinfunction "TX_TX") (pintype "bidirectional"))
    )
    (net (code "113") (name "unconnected-(U$24-RSV-PadRSV@1)") (class "Default")
      (node (ref "U$24") (pin "RSV@1") (pinfunction "RSV_RSV@1") (pintype "bidirectional"))
    )
  )
)
